# 02-CPU_BOARD.net
KiCad netlist of a schematic drawn in Altium Designer
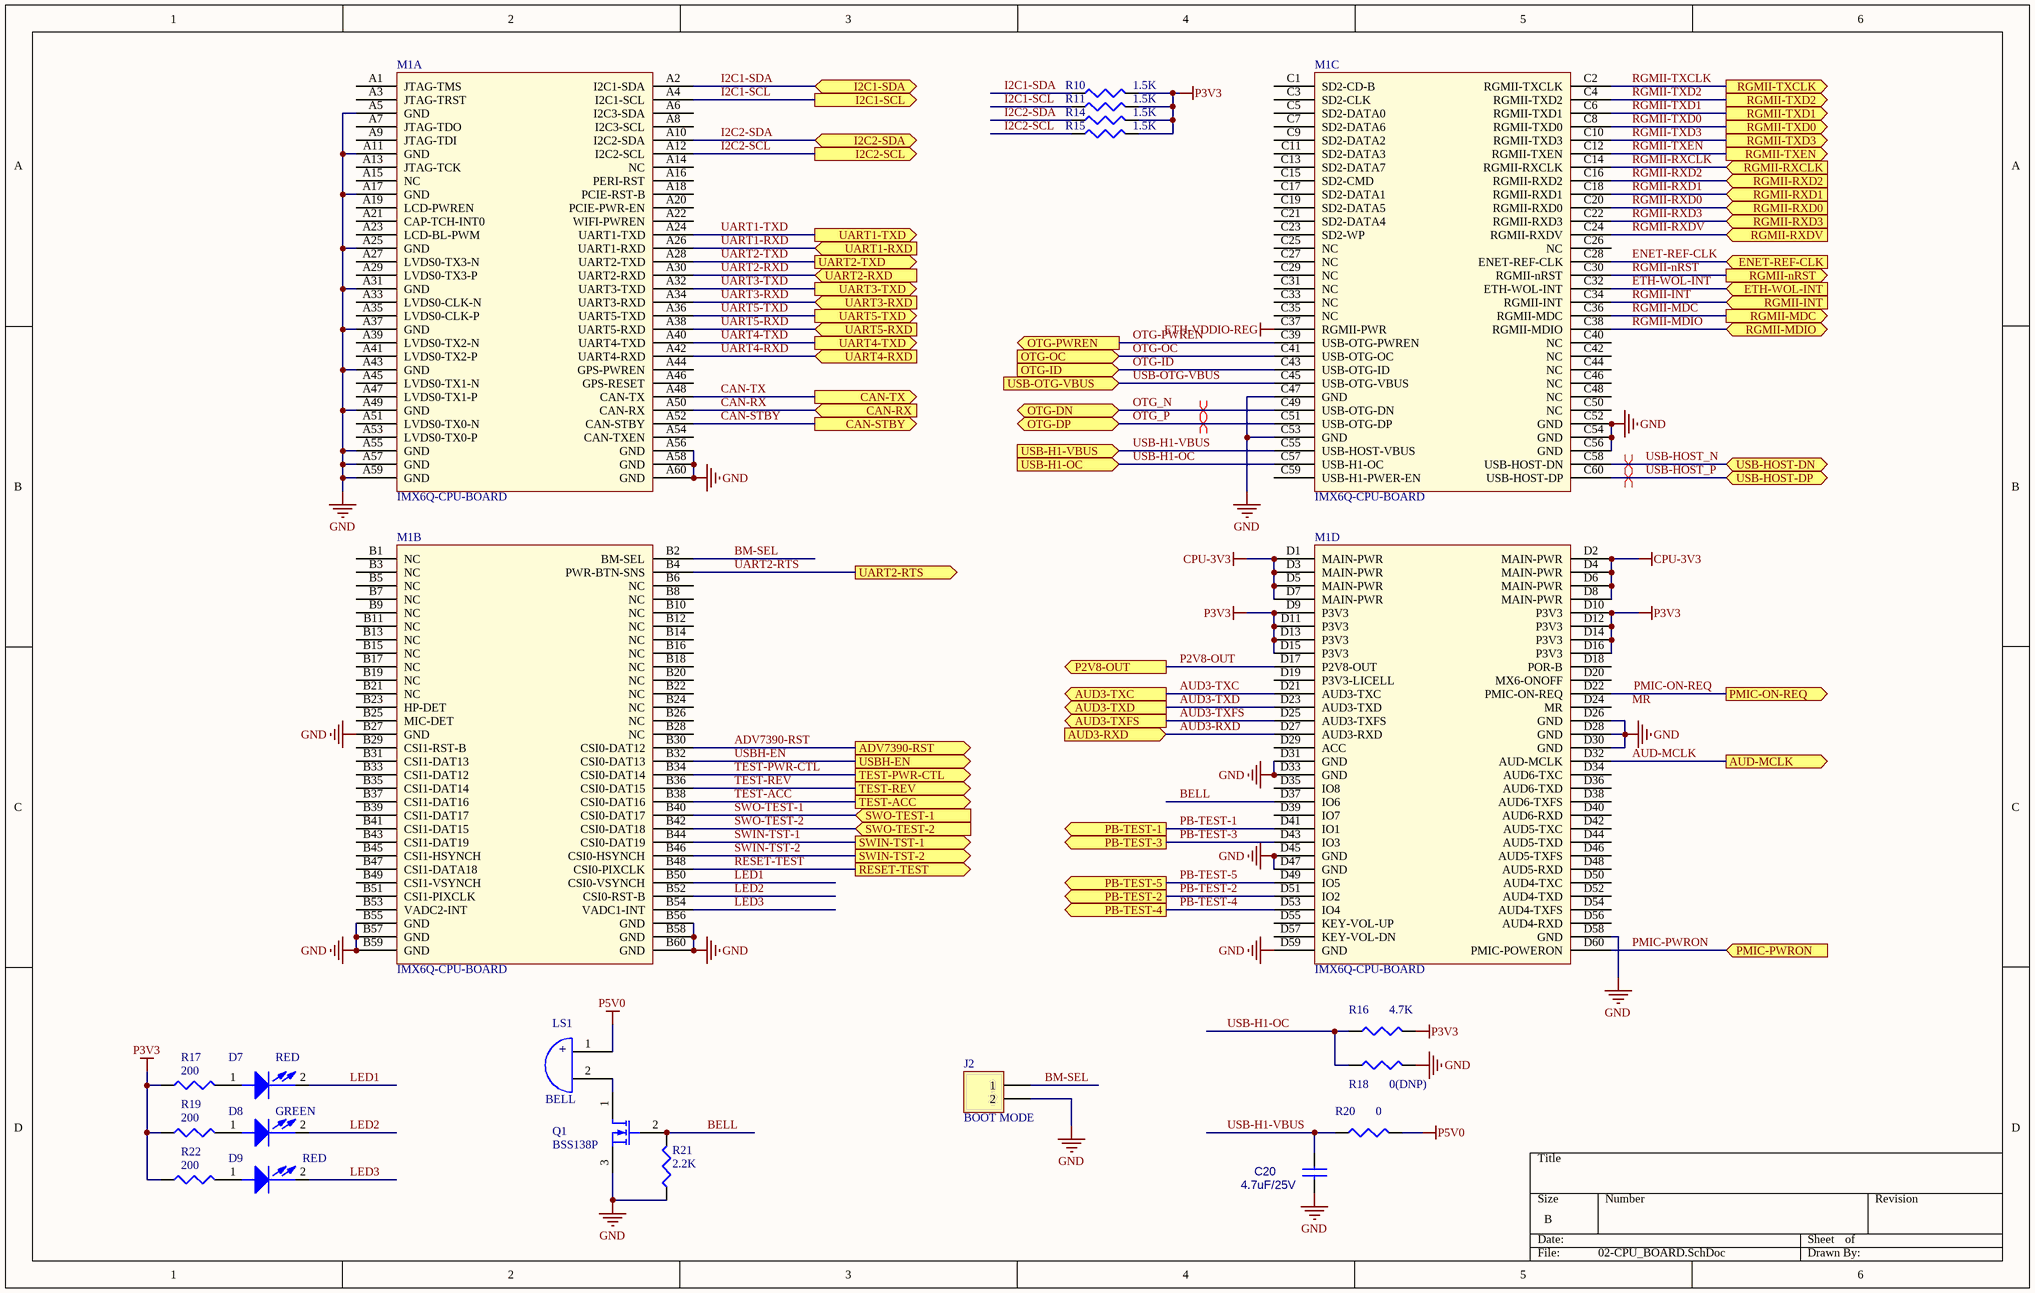
[diagram p0: 02-CPU_BOARD.SchDoc]

(export (version "E")
  (design (tool "Eeschema 10.0.6"))
  (components
    (comp (ref "C20") (value "4.7uF/25V") (libsource (lib "*") (part "CAP_Dup1")))
    (comp (ref "D7") (value "RED") (footprint "LED-3MM") (libsource (lib "*") (part "LN01401_1")))
    (comp (ref "D8") (value "GREEN") (footprint "LED-3MM") (libsource (lib "*") (part "LN01401_1")))
    (comp (ref "D9") (value "RED") (footprint "LED-3MM") (libsource (lib "*") (part "LN01401_1")))
    (comp (ref "J2")
      (value "BOOT MODE")
      (footprint "HDR1X2")
      (description "Header, 2-Pin")
      (fields (field (name "PUBLISHER") "Altium Limited"))
      (libsource (lib "Miscellaneous Connectors") (part "Header 2"))
    )
    (comp (ref "LS1") (value "BELL") (footprint "bell") (libsource (lib "Schlib") (part "BELL")))
    (comp (ref "M1")
      (value "IMX6Q-CPU-BOARD")
      (footprint "IMX6-CPU-BOARD")
      (libsource (lib "Schlib") (part "IMX6Q-CPU-BOARD"))
    )
    (comp (ref "Q1")
      (value "BSS138P")
      (footprint "NPN")
      (description "N-Channel MOSFET")
      (fields (field (name "PUBLISHER") "Altium Limited"))
      (libsource (lib "Miscellaneous Devices") (part "MOSFET-N"))
    )
    (comp (ref "R10") (value "1.5K") (footprint "0402") (libsource (lib "*") (part "CR16-1003FM")))
    (comp (ref "R11") (value "1.5K") (footprint "0402") (libsource (lib "*") (part "CR16-1003FM")))
    (comp (ref "R14") (value "1.5K") (footprint "0402") (libsource (lib "*") (part "CR16-1003FM")))
    (comp (ref "R15") (value "1.5K") (footprint "0402") (libsource (lib "*") (part "CR16-1003FM")))
    (comp (ref "R16") (value "4.7K") (footprint "0402") (libsource (lib "*") (part "CR16-1003FM")))
    (comp (ref "R17")
      (value "200")
      (footprint "0402")
      (description "Resistor")
      (fields (field (name "PUBLISHER") "Altium Limited"))
      (libsource (lib "Miscellaneous Devices") (part "Res3"))
    )
    (comp (ref "R18") (value "0(DNP)") (footprint "0402") (libsource (lib "*") (part "CR16-1003FM")))
    (comp (ref "R19")
      (value "200")
      (footprint "0402")
      (description "Resistor")
      (fields (field (name "PUBLISHER") "Altium Limited"))
      (libsource (lib "Miscellaneous Devices") (part "Res3"))
    )
    (comp (ref "R20") (value "0") (footprint "0402") (libsource (lib "*") (part "CR16-1003FM")))
    (comp (ref "R21")
      (value "2.2K")
      (footprint "0402")
      (description "Resistor")
      (fields (field (name "PUBLISHER") "Altium Limited"))
      (libsource (lib "Miscellaneous Devices") (part "Res3"))
    )
    (comp (ref "R22")
      (value "200")
      (footprint "0402")
      (description "Resistor")
      (fields (field (name "PUBLISHER") "Altium Limited"))
      (libsource (lib "Miscellaneous Devices") (part "Res3"))
    )
  )
  (nets
    (net (code "1") (name "/ADV7390-RST") (class "Default")
      (node (ref "M1") (pin "B30") (pinfunction "CSI0-DAT12_B30") (pintype "passive"))
    )
    (net (code "2") (name "/AUD-MCLK") (class "Default")
      (node (ref "M1") (pin "D32") (pinfunction "AUD-MCLK_D32") (pintype "passive"))
    )
    (net (code "3") (name "/AUD3-RXD") (class "Default")
      (node (ref "M1") (pin "D27") (pinfunction "AUD3-RXD_D27") (pintype "passive"))
    )
    (net (code "4") (name "/AUD3-TXC") (class "Default")
      (node (ref "M1") (pin "D21") (pinfunction "AUD3-TXC_D21") (pintype "passive"))
    )
    (net (code "5") (name "/AUD3-TXD") (class "Default")
      (node (ref "M1") (pin "D23") (pinfunction "AUD3-TXD_D23") (pintype "passive"))
    )
    (net (code "6") (name "/AUD3-TXFS") (class "Default")
      (node (ref "M1") (pin "D25") (pinfunction "AUD3-TXFS_D25") (pintype "passive"))
    )
    (net (code "7") (name "/BELL") (class "Default")
      (node (ref "M1") (pin "D37") (pinfunction "IO6_D37") (pintype "passive"))
      (node (ref "Q1") (pin "2") (pinfunction "G_2") (pintype "passive"))
      (node (ref "R21") (pin "1") (pinfunction "1_1") (pintype "passive"))
    )
    (net (code "8") (name "/BM-SEL") (class "Default")
      (node (ref "J2") (pin "1") (pinfunction "1_1") (pintype "passive"))
      (node (ref "M1") (pin "B2") (pinfunction "BM-SEL_B2") (pintype "passive"))
    )
    (net (code "9") (name "/CAN-RX") (class "Default")
      (node (ref "M1") (pin "A50") (pinfunction "CAN-RX_A50") (pintype "passive"))
    )
    (net (code "10") (name "/CAN-STBY") (class "Default")
      (node (ref "M1") (pin "A52") (pinfunction "CAN-STBY_A52") (pintype "passive"))
    )
    (net (code "11") (name "/CAN-TX") (class "Default")
      (node (ref "M1") (pin "A48") (pinfunction "CAN-TX_A48") (pintype "passive"))
    )
    (net (code "12") (name "/ENET-REF-CLK") (class "Default")
      (node (ref "M1") (pin "C28") (pinfunction "ENET-REF-CLK_C28") (pintype "passive"))
    )
    (net (code "13") (name "/ETH-WOL-INT") (class "Default")
      (node (ref "M1") (pin "C32") (pinfunction "ETH-WOL-INT_C32") (pintype "passive"))
    )
    (net (code "14") (name "/I2C1-SCL") (class "Default")
      (node (ref "M1") (pin "A4") (pinfunction "I2C1-SCL_A4") (pintype "passive"))
      (node (ref "R11") (pin "1") (pinfunction "1_1") (pintype "passive"))
    )
    (net (code "15") (name "/I2C1-SDA") (class "Default")
      (node (ref "M1") (pin "A2") (pinfunction "I2C1-SDA_A2") (pintype "passive"))
      (node (ref "R10") (pin "1") (pinfunction "1_1") (pintype "passive"))
    )
    (net (code "16") (name "/I2C2-SCL") (class "Default")
      (node (ref "M1") (pin "A12") (pinfunction "I2C2-SCL_A12") (pintype "passive"))
      (node (ref "R15") (pin "1") (pinfunction "1_1") (pintype "passive"))
    )
    (net (code "17") (name "/I2C2-SDA") (class "Default")
      (node (ref "M1") (pin "A10") (pinfunction "I2C2-SDA_A10") (pintype "passive"))
      (node (ref "R14") (pin "1") (pinfunction "1_1") (pintype "passive"))
    )
    (net (code "18") (name "/LED1") (class "Default")
      (node (ref "D7") (pin "2") (pinfunction "CATHODE_2") (pintype "passive"))
      (node (ref "M1") (pin "B50") (pinfunction "CSI0-VSYNCH_B50") (pintype "passive"))
    )
    (net (code "19") (name "/LED2") (class "Default")
      (node (ref "D8") (pin "2") (pinfunction "CATHODE_2") (pintype "passive"))
      (node (ref "M1") (pin "B52") (pinfunction "CSI0-RST-B_B52") (pintype "passive"))
    )
    (net (code "20") (name "/LED3") (class "Default")
      (node (ref "D9") (pin "2") (pinfunction "CATHODE_2") (pintype "passive"))
      (node (ref "M1") (pin "B54") (pinfunction "VADC1-INT_B54") (pintype "passive"))
    )
    (net (code "22") (name "/OTG-ID") (class "Default")
      (node (ref "M1") (pin "C43") (pinfunction "USB-OTG-ID_C43") (pintype "passive"))
    )
    (net (code "23") (name "/OTG-OC") (class "Default")
      (node (ref "M1") (pin "C41") (pinfunction "USB-OTG-OC_C41") (pintype "passive"))
    )
    (net (code "24") (name "/OTG-PWREN") (class "Default")
      (node (ref "M1") (pin "C39") (pinfunction "USB-OTG-PWREN_C39") (pintype "passive"))
    )
    (net (code "25") (name "/OTG_N") (class "Default")
      (node (ref "M1") (pin "C49") (pinfunction "USB-OTG-DN_C49") (pintype "passive"))
    )
    (net (code "26") (name "/OTG_P") (class "Default")
      (node (ref "M1") (pin "C51") (pinfunction "USB-OTG-DP_C51") (pintype "passive"))
    )
    (net (code "27") (name "/P2V8-OUT") (class "Default")
      (node (ref "M1") (pin "D17") (pinfunction "P2V8-OUT_D17") (pintype "passive"))
    )
    (net (code "28") (name "/PB-TEST-1") (class "Default")
      (node (ref "M1") (pin "D41") (pinfunction "IO1_D41") (pintype "passive"))
    )
    (net (code "29") (name "/PB-TEST-2") (class "Default")
      (node (ref "M1") (pin "D51") (pinfunction "IO2_D51") (pintype "passive"))
    )
    (net (code "30") (name "/PB-TEST-3") (class "Default")
      (node (ref "M1") (pin "D43") (pinfunction "IO3_D43") (pintype "passive"))
    )
    (net (code "31") (name "/PB-TEST-4") (class "Default")
      (node (ref "M1") (pin "D53") (pinfunction "IO4_D53") (pintype "passive"))
    )
    (net (code "32") (name "/PB-TEST-5") (class "Default")
      (node (ref "M1") (pin "D49") (pinfunction "IO5_D49") (pintype "passive"))
    )
    (net (code "33") (name "/PMIC-ON-REQ") (class "Default")
      (node (ref "M1") (pin "D22") (pinfunction "PMIC-ON-REQ_D22") (pintype "passive"))
    )
    (net (code "34") (name "/PMIC-PWRON") (class "Default")
      (node (ref "M1") (pin "D60") (pinfunction "PMIC-POWERON_D60") (pintype "passive"))
    )
    (net (code "35") (name "/RESET-TEST") (class "Default")
      (node (ref "M1") (pin "B48") (pinfunction "CSI0-PIXCLK_B48") (pintype "passive"))
    )
    (net (code "36") (name "/RGMII-INT") (class "Default")
      (node (ref "M1") (pin "C34") (pinfunction "RGMII-INT_C34") (pintype "passive"))
    )
    (net (code "37") (name "/RGMII-MDC") (class "Default")
      (node (ref "M1") (pin "C36") (pinfunction "RGMII-MDC_C36") (pintype "passive"))
    )
    (net (code "38") (name "/RGMII-MDIO") (class "Default")
      (node (ref "M1") (pin "C38") (pinfunction "RGMII-MDIO_C38") (pintype "passive"))
    )
    (net (code "39") (name "/RGMII-RXCLK") (class "Default")
      (node (ref "M1") (pin "C14") (pinfunction "RGMII-RXCLK_C14") (pintype "passive"))
    )
    (net (code "40") (name "/RGMII-RXD0") (class "Default")
      (node (ref "M1") (pin "C20") (pinfunction "RGMII-RXD0_C20") (pintype "passive"))
    )
    (net (code "41") (name "/RGMII-RXD1") (class "Default")
      (node (ref "M1") (pin "C18") (pinfunction "RGMII-RXD1_C18") (pintype "passive"))
    )
    (net (code "42") (name "/RGMII-RXD2") (class "Default")
      (node (ref "M1") (pin "C16") (pinfunction "RGMII-RXD2_C16") (pintype "passive"))
    )
    (net (code "43") (name "/RGMII-RXD3") (class "Default")
      (node (ref "M1") (pin "C22") (pinfunction "RGMII-RXD3_C22") (pintype "passive"))
    )
    (net (code "44") (name "/RGMII-RXDV") (class "Default")
      (node (ref "M1") (pin "C24") (pinfunction "RGMII-RXDV_C24") (pintype "passive"))
    )
    (net (code "45") (name "/RGMII-TXCLK") (class "Default")
      (node (ref "M1") (pin "C2") (pinfunction "RGMII-TXCLK_C2") (pintype "passive"))
    )
    (net (code "46") (name "/RGMII-TXD0") (class "Default")
      (node (ref "M1") (pin "C8") (pinfunction "RGMII-TXD0_C8") (pintype "passive"))
    )
    (net (code "47") (name "/RGMII-TXD1") (class "Default")
      (node (ref "M1") (pin "C6") (pinfunction "RGMII-TXD1_C6") (pintype "passive"))
    )
    (net (code "48") (name "/RGMII-TXD2") (class "Default")
      (node (ref "M1") (pin "C4") (pinfunction "RGMII-TXD2_C4") (pintype "passive"))
    )
    (net (code "49") (name "/RGMII-TXD3") (class "Default")
      (node (ref "M1") (pin "C10") (pinfunction "RGMII-TXD3_C10") (pintype "passive"))
    )
    (net (code "50") (name "/RGMII-TXEN") (class "Default")
      (node (ref "M1") (pin "C12") (pinfunction "RGMII-TXEN_C12") (pintype "passive"))
    )
    (net (code "51") (name "/RGMII-nRST") (class "Default")
      (node (ref "M1") (pin "C30") (pinfunction "RGMII-nRST_C30") (pintype "passive"))
    )
    (net (code "52") (name "/SWIN-TST-1") (class "Default")
      (node (ref "M1") (pin "B44") (pinfunction "CSI0-DAT19_B44") (pintype "passive"))
    )
    (net (code "53") (name "/SWIN-TST-2") (class "Default")
      (node (ref "M1") (pin "B46") (pinfunction "CSI0-HSYNCH_B46") (pintype "passive"))
    )
    (net (code "54") (name "/SWO-TEST-1") (class "Default")
      (node (ref "M1") (pin "B40") (pinfunction "CSI0-DAT17_B40") (pintype "passive"))
    )
    (net (code "55") (name "/SWO-TEST-2") (class "Default")
      (node (ref "M1") (pin "B42") (pinfunction "CSI0-DAT18_B42") (pintype "passive"))
    )
    (net (code "56") (name "/TEST-ACC") (class "Default")
      (node (ref "M1") (pin "B38") (pinfunction "CSI0-DAT16_B38") (pintype "passive"))
    )
    (net (code "57") (name "/TEST-PWR-CTL") (class "Default")
      (node (ref "M1") (pin "B34") (pinfunction "CSI0-DAT14_B34") (pintype "passive"))
    )
    (net (code "58") (name "/TEST-REV") (class "Default")
      (node (ref "M1") (pin "B36") (pinfunction "CSI0-DAT15_B36") (pintype "passive"))
    )
    (net (code "59") (name "/UART1-RXD") (class "Default")
      (node (ref "M1") (pin "A26") (pinfunction "UART1-RXD_A26") (pintype "passive"))
    )
    (net (code "60") (name "/UART1-TXD") (class "Default")
      (node (ref "M1") (pin "A24") (pinfunction "UART1-TXD_A24") (pintype "passive"))
    )
    (net (code "61") (name "/UART2-RTS") (class "Default")
      (node (ref "M1") (pin "B4") (pinfunction "PWR-BTN-SNS_B4") (pintype "passive"))
    )
    (net (code "62") (name "/UART2-RXD") (class "Default")
      (node (ref "M1") (pin "A30") (pinfunction "UART2-RXD_A30") (pintype "passive"))
    )
    (net (code "63") (name "/UART2-TXD") (class "Default")
      (node (ref "M1") (pin "A28") (pinfunction "UART2-TXD_A28") (pintype "passive"))
    )
    (net (code "64") (name "/UART3-RXD") (class "Default")
      (node (ref "M1") (pin "A34") (pinfunction "UART3-RXD_A34") (pintype "passive"))
    )
    (net (code "65") (name "/UART3-TXD") (class "Default")
      (node (ref "M1") (pin "A32") (pinfunction "UART3-TXD_A32") (pintype "passive"))
    )
    (net (code "66") (name "/UART4-RXD") (class "Default")
      (node (ref "M1") (pin "A42") (pinfunction "UART4-RXD_A42") (pintype "passive"))
    )
    (net (code "67") (name "/UART4-TXD") (class "Default")
      (node (ref "M1") (pin "A40") (pinfunction "UART4-TXD_A40") (pintype "passive"))
    )
    (net (code "68") (name "/UART5-RXD") (class "Default")
      (node (ref "M1") (pin "A38") (pinfunction "UART5-RXD_A38") (pintype "passive"))
    )
    (net (code "69") (name "/UART5-TXD") (class "Default")
      (node (ref "M1") (pin "A36") (pinfunction "UART5-TXD_A36") (pintype "passive"))
    )
    (net (code "70") (name "/USB-H1-OC") (class "Default")
      (node (ref "M1") (pin "C57") (pinfunction "USB-H1-OC_C57") (pintype "passive"))
      (node (ref "R16") (pin "1") (pinfunction "1_1") (pintype "passive"))
      (node (ref "R18") (pin "1") (pinfunction "1_1") (pintype "passive"))
    )
    (net (code "71") (name "/USB-H1-VBUS") (class "Default")
      (node (ref "C20") (pin "1") (pinfunction "1_1") (pintype "passive"))
      (node (ref "M1") (pin "C55") (pinfunction "USB-HOST-VBUS_C55") (pintype "passive"))
      (node (ref "R20") (pin "1") (pinfunction "1_1") (pintype "passive"))
    )
    (net (code "72") (name "/USB-HOST_N") (class "Default")
      (node (ref "M1") (pin "C58") (pinfunction "USB-HOST-DN_C58") (pintype "passive"))
    )
    (net (code "73") (name "/USB-HOST_P") (class "Default")
      (node (ref "M1") (pin "C60") (pinfunction "USB-HOST-DP_C60") (pintype "passive"))
    )
    (net (code "74") (name "/USB-OTG-VBUS") (class "Default")
      (node (ref "M1") (pin "C45") (pinfunction "USB-OTG-VBUS_C45") (pintype "passive"))
    )
    (net (code "75") (name "/USBH-EN") (class "Default")
      (node (ref "M1") (pin "B32") (pinfunction "CSI0-DAT13_B32") (pintype "passive"))
    )
    (net (code "76") (name "CPU-3V3") (class "Default")
      (node (ref "M1") (pin "D1") (pinfunction "MAIN-PWR_D1") (pintype "passive"))
      (node (ref "M1") (pin "D2") (pinfunction "MAIN-PWR_D2") (pintype "passive"))
      (node (ref "M1") (pin "D3") (pinfunction "MAIN-PWR_D3") (pintype "passive"))
      (node (ref "M1") (pin "D4") (pinfunction "MAIN-PWR_D4") (pintype "passive"))
      (node (ref "M1") (pin "D5") (pinfunction "MAIN-PWR_D5") (pintype "passive"))
      (node (ref "M1") (pin "D6") (pinfunction "MAIN-PWR_D6") (pintype "passive"))
      (node (ref "M1") (pin "D7") (pinfunction "MAIN-PWR_D7") (pintype "passive"))
      (node (ref "M1") (pin "D8") (pinfunction "MAIN-PWR_D8") (pintype "passive"))
    )
    (net (code "77") (name "ETH-VDDIO-REG") (class "Default")
      (node (ref "M1") (pin "C37") (pinfunction "RGMII-PWR_C37") (pintype "passive"))
    )
    (net (code "78") (name "GND") (class "Default")
      (node (ref "C20") (pin "2") (pinfunction "2_2") (pintype "passive"))
      (node (ref "J2") (pin "2") (pinfunction "2_2") (pintype "passive"))
      (node (ref "M1") (pin "A11") (pinfunction "GND_A11") (pintype "passive"))
      (node (ref "M1") (pin "A17") (pinfunction "GND_A17") (pintype "passive"))
      (node (ref "M1") (pin "A25") (pinfunction "GND_A25") (pintype "passive"))
      (node (ref "M1") (pin "A31") (pinfunction "GND_A31") (pintype "passive"))
      (node (ref "M1") (pin "A37") (pinfunction "GND_A37") (pintype "passive"))
      (node (ref "M1") (pin "A43") (pinfunction "GND_A43") (pintype "passive"))
      (node (ref "M1") (pin "A49") (pinfunction "GND_A49") (pintype "passive"))
      (node (ref "M1") (pin "A5") (pinfunction "GND_A5") (pintype "passive"))
      (node (ref "M1") (pin "A55") (pinfunction "GND_A55") (pintype "passive"))
      (node (ref "M1") (pin "A56") (pinfunction "GND_A56") (pintype "passive"))
      (node (ref "M1") (pin "A57") (pinfunction "GND_A57") (pintype "passive"))
      (node (ref "M1") (pin "A58") (pinfunction "GND_A58") (pintype "passive"))
      (node (ref "M1") (pin "A59") (pinfunction "GND_A59") (pintype "passive"))
      (node (ref "M1") (pin "A60") (pinfunction "GND_A60") (pintype "passive"))
      (node (ref "M1") (pin "B27") (pinfunction "GND_B27") (pintype "passive"))
      (node (ref "M1") (pin "B55") (pinfunction "GND_B55") (pintype "passive"))
      (node (ref "M1") (pin "B56") (pinfunction "GND_B56") (pintype "passive"))
      (node (ref "M1") (pin "B57") (pinfunction "GND_B57") (pintype "passive"))
      (node (ref "M1") (pin "B58") (pinfunction "GND_B58") (pintype "passive"))
      (node (ref "M1") (pin "B59") (pinfunction "GND_B59") (pintype "passive"))
      (node (ref "M1") (pin "B60") (pinfunction "GND_B60") (pintype "passive"))
      (node (ref "M1") (pin "C47") (pinfunction "GND_C47") (pintype "passive"))
      (node (ref "M1") (pin "C52") (pinfunction "GND_C52") (pintype "passive"))
      (node (ref "M1") (pin "C53") (pinfunction "GND_C53") (pintype "passive"))
      (node (ref "M1") (pin "C54") (pinfunction "GND_C54") (pintype "passive"))
      (node (ref "M1") (pin "C56") (pinfunction "GND_C56") (pintype "passive"))
      (node (ref "M1") (pin "D26") (pinfunction "GND_D26") (pintype "passive"))
      (node (ref "M1") (pin "D28") (pinfunction "GND_D28") (pintype "passive"))
      (node (ref "M1") (pin "D30") (pinfunction "GND_D30") (pintype "passive"))
      (node (ref "M1") (pin "D31") (pinfunction "GND_D31") (pintype "passive"))
      (node (ref "M1") (pin "D33") (pinfunction "GND_D33") (pintype "passive"))
      (node (ref "M1") (pin "D45") (pinfunction "GND_D45") (pintype "passive"))
      (node (ref "M1") (pin "D47") (pinfunction "GND_D47") (pintype "passive"))
      (node (ref "M1") (pin "D58") (pinfunction "GND_D58") (pintype "passive"))
      (node (ref "M1") (pin "D59") (pinfunction "GND_D59") (pintype "passive"))
      (node (ref "Q1") (pin "3") (pinfunction "S_3") (pintype "passive"))
      (node (ref "R18") (pin "2") (pinfunction "2_2") (pintype "passive"))
      (node (ref "R21") (pin "2") (pinfunction "2_2") (pintype "passive"))
    )
    (net (code "79") (name "Net-(D7-ANODE)") (class "Default")
      (node (ref "D7") (pin "1") (pinfunction "ANODE_1") (pintype "passive"))
      (node (ref "R17") (pin "2") (pinfunction "2_2") (pintype "passive"))
    )
    (net (code "80") (name "Net-(D8-ANODE)") (class "Default")
      (node (ref "D8") (pin "1") (pinfunction "ANODE_1") (pintype "passive"))
      (node (ref "R19") (pin "2") (pinfunction "2_2") (pintype "passive"))
    )
    (net (code "81") (name "Net-(D9-ANODE)") (class "Default")
      (node (ref "D9") (pin "1") (pinfunction "ANODE_1") (pintype "passive"))
      (node (ref "R22") (pin "2") (pinfunction "2_2") (pintype "passive"))
    )
    (net (code "82") (name "Net-(Q1-D)") (class "Default")
      (node (ref "LS1") (pin "2") (pinfunction "2_2") (pintype "passive"))
      (node (ref "Q1") (pin "1") (pinfunction "D_1") (pintype "passive"))
    )
    (net (code "83") (name "P3V3") (class "Default")
      (node (ref "M1") (pin "D10") (pinfunction "P3V3_D10") (pintype "passive"))
      (node (ref "M1") (pin "D11") (pinfunction "P3V3_D11") (pintype "passive"))
      (node (ref "M1") (pin "D12") (pinfunction "P3V3_D12") (pintype "passive"))
      (node (ref "M1") (pin "D13") (pinfunction "P3V3_D13") (pintype "passive"))
      (node (ref "M1") (pin "D14") (pinfunction "P3V3_D14") (pintype "passive"))
      (node (ref "M1") (pin "D15") (pinfunction "P3V3_D15") (pintype "passive"))
      (node (ref "M1") (pin "D16") (pinfunction "P3V3_D16") (pintype "passive"))
      (node (ref "M1") (pin "D9") (pinfunction "P3V3_D9") (pintype "passive"))
      (node (ref "R10") (pin "2") (pinfunction "2_2") (pintype "passive"))
      (node (ref "R11") (pin "2") (pinfunction "2_2") (pintype "passive"))
      (node (ref "R14") (pin "2") (pinfunction "2_2") (pintype "passive"))
      (node (ref "R15") (pin "2") (pinfunction "2_2") (pintype "passive"))
      (node (ref "R16") (pin "2") (pinfunction "2_2") (pintype "passive"))
      (node (ref "R17") (pin "1") (pinfunction "1_1") (pintype "passive"))
      (node (ref "R19") (pin "1") (pinfunction "1_1") (pintype "passive"))
      (node (ref "R22") (pin "1") (pinfunction "1_1") (pintype "passive"))
    )
    (net (code "84") (name "P5V0") (class "Default")
      (node (ref "LS1") (pin "1") (pinfunction "1_1") (pintype "passive"))
      (node (ref "R20") (pin "2") (pinfunction "2_2") (pintype "passive"))
    )
    (net (code "85") (name "unconnected-(M1A-CAN-TXEN-PadA54)") (class "Default")
      (node (ref "M1") (pin "A54") (pinfunction "CAN-TXEN_A54") (pintype "passive"))
    )
    (net (code "86") (name "unconnected-(M1A-CAP-TCH-INT0-PadA21)") (class "Default")
      (node (ref "M1") (pin "A21") (pinfunction "CAP-TCH-INT0_A21") (pintype "passive"))
    )
    (net (code "87") (name "unconnected-(M1A-GPS-PWREN-PadA44)") (class "Default")
      (node (ref "M1") (pin "A44") (pinfunction "GPS-PWREN_A44") (pintype "passive"))
    )
    (net (code "88") (name "unconnected-(M1A-GPS-RESET-PadA46)") (class "Default")
      (node (ref "M1") (pin "A46") (pinfunction "GPS-RESET_A46") (pintype "passive"))
    )
    (net (code "89") (name "unconnected-(M1A-I2C3-SCL-PadA8)") (class "Default")
      (node (ref "M1") (pin "A8") (pinfunction "I2C3-SCL_A8") (pintype "passive"))
    )
    (net (code "90") (name "unconnected-(M1A-I2C3-SDA-PadA6)") (class "Default")
      (node (ref "M1") (pin "A6") (pinfunction "I2C3-SDA_A6") (pintype "passive"))
    )
    (net (code "91") (name "unconnected-(M1A-JTAG-TCK-PadA13)") (class "Default")
      (node (ref "M1") (pin "A13") (pinfunction "JTAG-TCK_A13") (pintype "passive"))
    )
    (net (code "92") (name "unconnected-(M1A-JTAG-TDI-PadA9)") (class "Default")
      (node (ref "M1") (pin "A9") (pinfunction "JTAG-TDI_A9") (pintype "passive"))
    )
    (net (code "93") (name "unconnected-(M1A-JTAG-TDO-PadA7)") (class "Default")
      (node (ref "M1") (pin "A7") (pinfunction "JTAG-TDO_A7") (pintype "passive"))
    )
    (net (code "94") (name "unconnected-(M1A-JTAG-TMS-PadA1)") (class "Default")
      (node (ref "M1") (pin "A1") (pinfunction "JTAG-TMS_A1") (pintype "passive"))
    )
    (net (code "95") (name "unconnected-(M1A-JTAG-TRST-PadA3)") (class "Default")
      (node (ref "M1") (pin "A3") (pinfunction "JTAG-TRST_A3") (pintype "passive"))
    )
    (net (code "96") (name "unconnected-(M1A-LCD-BL-PWM-PadA23)") (class "Default")
      (node (ref "M1") (pin "A23") (pinfunction "LCD-BL-PWM_A23") (pintype "passive"))
    )
    (net (code "97") (name "unconnected-(M1A-LCD-PWREN-PadA19)") (class "Default")
      (node (ref "M1") (pin "A19") (pinfunction "LCD-PWREN_A19") (pintype "passive"))
    )
    (net (code "98") (name "unconnected-(M1A-LVDS0-CLK-N-PadA33)") (class "Default")
      (node (ref "M1") (pin "A33") (pinfunction "LVDS0-CLK-N_A33") (pintype "passive"))
    )
    (net (code "99") (name "unconnected-(M1A-LVDS0-CLK-P-PadA35)") (class "Default")
      (node (ref "M1") (pin "A35") (pinfunction "LVDS0-CLK-P_A35") (pintype "passive"))
    )
    (net (code "100") (name "unconnected-(M1A-LVDS0-TX0-N-PadA51)") (class "Default")
      (node (ref "M1") (pin "A51") (pinfunction "LVDS0-TX0-N_A51") (pintype "passive"))
    )
    (net (code "101") (name "unconnected-(M1A-LVDS0-TX0-P-PadA53)") (class "Default")
      (node (ref "M1") (pin "A53") (pinfunction "LVDS0-TX0-P_A53") (pintype "passive"))
    )
    (net (code "102") (name "unconnected-(M1A-LVDS0-TX1-N-PadA45)") (class "Default")
      (node (ref "M1") (pin "A45") (pinfunction "LVDS0-TX1-N_A45") (pintype "passive"))
    )
    (net (code "103") (name "unconnected-(M1A-LVDS0-TX1-P-PadA47)") (class "Default")
      (node (ref "M1") (pin "A47") (pinfunction "LVDS0-TX1-P_A47") (pintype "passive"))
    )
    (net (code "104") (name "unconnected-(M1A-LVDS0-TX2-N-PadA39)") (class "Default")
      (node (ref "M1") (pin "A39") (pinfunction "LVDS0-TX2-N_A39") (pintype "passive"))
    )
    (net (code "105") (name "unconnected-(M1A-LVDS0-TX2-P-PadA41)") (class "Default")
      (node (ref "M1") (pin "A41") (pinfunction "LVDS0-TX2-P_A41") (pintype "passive"))
    )
    (net (code "106") (name "unconnected-(M1A-LVDS0-TX3-N-PadA27)") (class "Default")
      (node (ref "M1") (pin "A27") (pinfunction "LVDS0-TX3-N_A27") (pintype "passive"))
    )
    (net (code "107") (name "unconnected-(M1A-LVDS0-TX3-P-PadA29)") (class "Default")
      (node (ref "M1") (pin "A29") (pinfunction "LVDS0-TX3-P_A29") (pintype "passive"))
    )
    (net (code "108") (name "unconnected-(M1A-NC-PadA14)") (class "Default")
      (node (ref "M1") (pin "A14") (pinfunction "NC_A14") (pintype "passive"))
    )
    (net (code "109") (name "unconnected-(M1A-NC-PadA15)") (class "Default")
      (node (ref "M1") (pin "A15") (pinfunction "NC_A15") (pintype "passive"))
    )
    (net (code "110") (name "unconnected-(M1A-PCIE-PWR-EN-PadA20)") (class "Default")
      (node (ref "M1") (pin "A20") (pinfunction "PCIE-PWR-EN_A20") (pintype "passive"))
    )
    (net (code "111") (name "unconnected-(M1A-PCIE-RST-B-PadA18)") (class "Default")
      (node (ref "M1") (pin "A18") (pinfunction "PCIE-RST-B_A18") (pintype "passive"))
    )
    (net (code "112") (name "unconnected-(M1A-PERI-RST-PadA16)") (class "Default")
      (node (ref "M1") (pin "A16") (pinfunction "PERI-RST_A16") (pintype "passive"))
    )
    (net (code "113") (name "unconnected-(M1A-WIFI-PWREN-PadA22)") (class "Default")
      (node (ref "M1") (pin "A22") (pinfunction "WIFI-PWREN_A22") (pintype "passive"))
    )
    (net (code "114") (name "unconnected-(M1B-CSI1-DAT12-PadB33)") (class "Default")
      (node (ref "M1") (pin "B33") (pinfunction "CSI1-DAT12_B33") (pintype "passive"))
    )
    (net (code "115") (name "unconnected-(M1B-CSI1-DAT13-PadB31)") (class "Default")
      (node (ref "M1") (pin "B31") (pinfunction "CSI1-DAT13_B31") (pintype "passive"))
    )
    (net (code "116") (name "unconnected-(M1B-CSI1-DAT14-PadB35)") (class "Default")
      (node (ref "M1") (pin "B35") (pinfunction "CSI1-DAT14_B35") (pintype "passive"))
    )
    (net (code "117") (name "unconnected-(M1B-CSI1-DAT15-PadB41)") (class "Default")
      (node (ref "M1") (pin "B41") (pinfunction "CSI1-DAT15_B41") (pintype "passive"))
    )
    (net (code "118") (name "unconnected-(M1B-CSI1-DAT16-PadB37)") (class "Default")
      (node (ref "M1") (pin "B37") (pinfunction "CSI1-DAT16_B37") (pintype "passive"))
    )
    (net (code "119") (name "unconnected-(M1B-CSI1-DAT17-PadB39)") (class "Default")
      (node (ref "M1") (pin "B39") (pinfunction "CSI1-DAT17_B39") (pintype "passive"))
    )
    (net (code "120") (name "unconnected-(M1B-CSI1-DAT19-PadB43)") (class "Default")
      (node (ref "M1") (pin "B43") (pinfunction "CSI1-DAT19_B43") (pintype "passive"))
    )
    (net (code "121") (name "unconnected-(M1B-CSI1-DATA18-PadB47)") (class "Default")
      (node (ref "M1") (pin "B47") (pinfunction "CSI1-DATA18_B47") (pintype "passive"))
    )
    (net (code "122") (name "unconnected-(M1B-CSI1-HSYNCH-PadB45)") (class "Default")
      (node (ref "M1") (pin "B45") (pinfunction "CSI1-HSYNCH_B45") (pintype "passive"))
    )
    (net (code "123") (name "unconnected-(M1B-CSI1-PIXCLK-PadB51)") (class "Default")
      (node (ref "M1") (pin "B51") (pinfunction "CSI1-PIXCLK_B51") (pintype "passive"))
    )
    (net (code "124") (name "unconnected-(M1B-CSI1-RST-B-PadB29)") (class "Default")
      (node (ref "M1") (pin "B29") (pinfunction "CSI1-RST-B_B29") (pintype "passive"))
    )
    (net (code "125") (name "unconnected-(M1B-CSI1-VSYNCH-PadB49)") (class "Default")
      (node (ref "M1") (pin "B49") (pinfunction "CSI1-VSYNCH_B49") (pintype "passive"))
    )
    (net (code "126") (name "unconnected-(M1B-HP-DET-PadB23)") (class "Default")
      (node (ref "M1") (pin "B23") (pinfunction "HP-DET_B23") (pintype "passive"))
    )
    (net (code "127") (name "unconnected-(M1B-MIC-DET-PadB25)") (class "Default")
      (node (ref "M1") (pin "B25") (pinfunction "MIC-DET_B25") (pintype "passive"))
    )
    (net (code "128") (name "unconnected-(M1B-NC-PadB1)") (class "Default")
      (node (ref "M1") (pin "B1") (pinfunction "NC_B1") (pintype "passive"))
    )
    (net (code "129") (name "unconnected-(M1B-NC-PadB3)") (class "Default")
      (node (ref "M1") (pin "B3") (pinfunction "NC_B3") (pintype "passive"))
    )
    (net (code "130") (name "unconnected-(M1B-NC-PadB5)") (class "Default")
      (node (ref "M1") (pin "B5") (pinfunction "NC_B5") (pintype "passive"))
    )
    (net (code "131") (name "unconnected-(M1B-NC-PadB6)") (class "Default")
      (node (ref "M1") (pin "B6") (pinfunction "NC_B6") (pintype "passive"))
    )
    (net (code "132") (name "unconnected-(M1B-NC-PadB7)") (class "Default")
      (node (ref "M1") (pin "B7") (pinfunction "NC_B7") (pintype "passive"))
    )
    (net (code "133") (name "unconnected-(M1B-NC-PadB8)") (class "Default")
      (node (ref "M1") (pin "B8") (pinfunction "NC_B8") (pintype "passive"))
    )
    (net (code "134") (name "unconnected-(M1B-NC-PadB9)") (class "Default")
      (node (ref "M1") (pin "B9") (pinfunction "NC_B9") (pintype "passive"))
    )
    (net (code "135") (name "unconnected-(M1B-NC-PadB10)") (class "Default")
      (node (ref "M1") (pin "B10") (pinfunction "NC_B10") (pintype "passive"))
    )
    (net (code "136") (name "unconnected-(M1B-NC-PadB11)") (class "Default")
      (node (ref "M1") (pin "B11") (pinfunction "NC_B11") (pintype "passive"))
    )
    (net (code "137") (name "unconnected-(M1B-NC-PadB12)") (class "Default")
      (node (ref "M1") (pin "B12") (pinfunction "NC_B12") (pintype "passive"))
    )
    (net (code "138") (name "unconnected-(M1B-NC-PadB13)") (class "Default")
      (node (ref "M1") (pin "B13") (pinfunction "NC_B13") (pintype "passive"))
    )
    (net (code "139") (name "unconnected-(M1B-NC-PadB14)") (class "Default")
      (node (ref "M1") (pin "B14") (pinfunction "NC_B14") (pintype "passive"))
    )
    (net (code "140") (name "unconnected-(M1B-NC-PadB15)") (class "Default")
      (node (ref "M1") (pin "B15") (pinfunction "NC_B15") (pintype "passive"))
    )
    (net (code "141") (name "unconnected-(M1B-NC-PadB16)") (class "Default")
      (node (ref "M1") (pin "B16") (pinfunction "NC_B16") (pintype "passive"))
    )
    (net (code "142") (name "unconnected-(M1B-NC-PadB17)") (class "Default")
      (node (ref "M1") (pin "B17") (pinfunction "NC_B17") (pintype "passive"))
    )
    (net (code "143") (name "unconnected-(M1B-NC-PadB18)") (class "Default")
      (node (ref "M1") (pin "B18") (pinfunction "NC_B18") (pintype "passive"))
    )
    (net (code "144") (name "unconnected-(M1B-NC-PadB19)") (class "Default")
      (node (ref "M1") (pin "B19") (pinfunction "NC_B19") (pintype "passive"))
    )
    (net (code "145") (name "unconnected-(M1B-NC-PadB20)") (class "Default")
      (node (ref "M1") (pin "B20") (pinfunction "NC_B20") (pintype "passive"))
    )
    (net (code "146") (name "unconnected-(M1B-NC-PadB21)") (class "Default")
      (node (ref "M1") (pin "B21") (pinfunction "NC_B21") (pintype "passive"))
    )
    (net (code "147") (name "unconnected-(M1B-NC-PadB22)") (class "Default")
      (node (ref "M1") (pin "B22") (pinfunction "NC_B22") (pintype "passive"))
    )
    (net (code "148") (name "unconnected-(M1B-NC-PadB24)") (class "Default")
      (node (ref "M1") (pin "B24") (pinfunction "NC_B24") (pintype "passive"))
    )
    (net (code "149") (name "unconnected-(M1B-NC-PadB26)") (class "Default")
      (node (ref "M1") (pin "B26") (pinfunction "NC_B26") (pintype "passive"))
    )
    (net (code "150") (name "unconnected-(M1B-NC-PadB28)") (class "Default")
      (node (ref "M1") (pin "B28") (pinfunction "NC_B28") (pintype "passive"))
    )
    (net (code "151") (name "unconnected-(M1B-VADC2-INT-PadB53)") (class "Default")
      (node (ref "M1") (pin "B53") (pinfunction "VADC2-INT_B53") (pintype "passive"))
    )
    (net (code "152") (name "unconnected-(M1C-NC-PadC25)") (class "Default")
      (node (ref "M1") (pin "C25") (pinfunction "NC_C25") (pintype "passive"))
    )
    (net (code "153") (name "unconnected-(M1C-NC-PadC26)") (class "Default")
      (node (ref "M1") (pin "C26") (pinfunction "NC_C26") (pintype "passive"))
    )
    (net (code "154") (name "unconnected-(M1C-NC-PadC27)") (class "Default")
      (node (ref "M1") (pin "C27") (pinfunction "NC_C27") (pintype "passive"))
    )
    (net (code "155") (name "unconnected-(M1C-NC-PadC29)") (class "Default")
      (node (ref "M1") (pin "C29") (pinfunction "NC_C29") (pintype "passive"))
    )
    (net (code "156") (name "unconnected-(M1C-NC-PadC31)") (class "Default")
      (node (ref "M1") (pin "C31") (pinfunction "NC_C31") (pintype "passive"))
    )
    (net (code "157") (name "unconnected-(M1C-NC-PadC33)") (class "Default")
      (node (ref "M1") (pin "C33") (pinfunction "NC_C33") (pintype "passive"))
    )
    (net (code "158") (name "unconnected-(M1C-NC-PadC35)") (class "Default")
      (node (ref "M1") (pin "C35") (pinfunction "NC_C35") (pintype "passive"))
    )
    (net (code "159") (name "unconnected-(M1C-NC-PadC40)") (class "Default")
      (node (ref "M1") (pin "C40") (pinfunction "NC_C40") (pintype "passive"))
    )
    (net (code "160") (name "unconnected-(M1C-NC-PadC42)") (class "Default")
      (node (ref "M1") (pin "C42") (pinfunction "NC_C42") (pintype "passive"))
    )
    (net (code "161") (name "unconnected-(M1C-NC-PadC44)") (class "Default")
      (node (ref "M1") (pin "C44") (pinfunction "NC_C44") (pintype "passive"))
    )
    (net (code "162") (name "unconnected-(M1C-NC-PadC46)") (class "Default")
      (node (ref "M1") (pin "C46") (pinfunction "NC_C46") (pintype "passive"))
    )
    (net (code "163") (name "unconnected-(M1C-NC-PadC48)") (class "Default")
      (node (ref "M1") (pin "C48") (pinfunction "NC_C48") (pintype "passive"))
    )
    (net (code "164") (name "unconnected-(M1C-NC-PadC50)") (class "Default")
      (node (ref "M1") (pin "C50") (pinfunction "NC_C50") (pintype "passive"))
    )
    (net (code "165") (name "unconnected-(M1C-SD2-CD-B-PadC1)") (class "Default")
      (node (ref "M1") (pin "C1") (pinfunction "SD2-CD-B_C1") (pintype "passive"))
    )
    (net (code "166") (name "unconnected-(M1C-SD2-CLK-PadC3)") (class "Default")
      (node (ref "M1") (pin "C3") (pinfunction "SD2-CLK_C3") (pintype "passive"))
    )
    (net (code "167") (name "unconnected-(M1C-SD2-CMD-PadC15)") (class "Default")
      (node (ref "M1") (pin "C15") (pinfunction "SD2-CMD_C15") (pintype "passive"))
    )
    (net (code "168") (name "unconnected-(M1C-SD2-DATA0-PadC5)") (class "Default")
      (node (ref "M1") (pin "C5") (pinfunction "SD2-DATA0_C5") (pintype "passive"))
    )
    (net (code "169") (name "unconnected-(M1C-SD2-DATA1-PadC17)") (class "Default")
      (node (ref "M1") (pin "C17") (pinfunction "SD2-DATA1_C17") (pintype "passive"))
    )
    (net (code "170") (name "unconnected-(M1C-SD2-DATA2-PadC9)") (class "Default")
      (node (ref "M1") (pin "C9") (pinfunction "SD2-DATA2_C9") (pintype "passive"))
    )
    (net (code "171") (name "unconnected-(M1C-SD2-DATA3-PadC11)") (class "Default")
      (node (ref "M1") (pin "C11") (pinfunction "SD2-DATA3_C11") (pintype "passive"))
    )
    (net (code "172") (name "unconnected-(M1C-SD2-DATA4-PadC21)") (class "Default")
      (node (ref "M1") (pin "C21") (pinfunction "SD2-DATA4_C21") (pintype "passive"))
    )
    (net (code "173") (name "unconnected-(M1C-SD2-DATA5-PadC19)") (class "Default")
      (node (ref "M1") (pin "C19") (pinfunction "SD2-DATA5_C19") (pintype "passive"))
    )
    (net (code "174") (name "unconnected-(M1C-SD2-DATA6-PadC7)") (class "Default")
      (node (ref "M1") (pin "C7") (pinfunction "SD2-DATA6_C7") (pintype "passive"))
    )
    (net (code "175") (name "unconnected-(M1C-SD2-DATA7-PadC13)") (class "Default")
      (node (ref "M1") (pin "C13") (pinfunction "SD2-DATA7_C13") (pintype "passive"))
    )
    (net (code "176") (name "unconnected-(M1C-SD2-WP-PadC23)") (class "Default")
      (node (ref "M1") (pin "C23") (pinfunction "SD2-WP_C23") (pintype "passive"))
    )
    (net (code "177") (name "unconnected-(M1C-USB-H1-PWER-EN-PadC59)") (class "Default")
      (node (ref "M1") (pin "C59") (pinfunction "USB-H1-PWER-EN_C59") (pintype "passive"))
    )
    (net (code "178") (name "unconnected-(M1D-ACC-PadD29)") (class "Default")
      (node (ref "M1") (pin "D29") (pinfunction "ACC_D29") (pintype "passive"))
    )
    (net (code "179") (name "unconnected-(M1D-AUD4-RXD-PadD56)") (class "Default")
      (node (ref "M1") (pin "D56") (pinfunction "AUD4-RXD_D56") (pintype "passive"))
    )
    (net (code "180") (name "unconnected-(M1D-AUD4-TXC-PadD50)") (class "Default")
      (node (ref "M1") (pin "D50") (pinfunction "AUD4-TXC_D50") (pintype "passive"))
    )
    (net (code "181") (name "unconnected-(M1D-AUD4-TXD-PadD52)") (class "Default")
      (node (ref "M1") (pin "D52") (pinfunction "AUD4-TXD_D52") (pintype "passive"))
    )
    (net (code "182") (name "unconnected-(M1D-AUD4-TXFS-PadD54)") (class "Default")
      (node (ref "M1") (pin "D54") (pinfunction "AUD4-TXFS_D54") (pintype "passive"))
    )
    (net (code "183") (name "unconnected-(M1D-AUD5-RXD-PadD48)") (class "Default")
      (node (ref "M1") (pin "D48") (pinfunction "AUD5-RXD_D48") (pintype "passive"))
    )
    (net (code "184") (name "unconnected-(M1D-AUD5-TXC-PadD42)") (class "Default")
      (node (ref "M1") (pin "D42") (pinfunction "AUD5-TXC_D42") (pintype "passive"))
    )
    (net (code "185") (name "unconnected-(M1D-AUD5-TXD-PadD44)") (class "Default")
      (node (ref "M1") (pin "D44") (pinfunction "AUD5-TXD_D44") (pintype "passive"))
    )
    (net (code "186") (name "unconnected-(M1D-AUD5-TXFS-PadD46)") (class "Default")
      (node (ref "M1") (pin "D46") (pinfunction "AUD5-TXFS_D46") (pintype "passive"))
    )
    (net (code "187") (name "unconnected-(M1D-AUD6-RXD-PadD40)") (class "Default")
      (node (ref "M1") (pin "D40") (pinfunction "AUD6-RXD_D40") (pintype "passive"))
    )
    (net (code "188") (name "unconnected-(M1D-AUD6-TXC-PadD34)") (class "Default")
      (node (ref "M1") (pin "D34") (pinfunction "AUD6-TXC_D34") (pintype "passive"))
    )
    (net (code "189") (name "unconnected-(M1D-AUD6-TXD-PadD36)") (class "Default")
      (node (ref "M1") (pin "D36") (pinfunction "AUD6-TXD_D36") (pintype "passive"))
    )
    (net (code "190") (name "unconnected-(M1D-AUD6-TXFS-PadD38)") (class "Default")
      (node (ref "M1") (pin "D38") (pinfunction "AUD6-TXFS_D38") (pintype "passive"))
    )
    (net (code "191") (name "unconnected-(M1D-IO7-PadD39)") (class "Default")
      (node (ref "M1") (pin "D39") (pinfunction "IO7_D39") (pintype "passive"))
    )
    (net (code "192") (name "unconnected-(M1D-IO8-PadD35)") (class "Default")
      (node (ref "M1") (pin "D35") (pinfunction "IO8_D35") (pintype "passive"))
    )
    (net (code "193") (name "unconnected-(M1D-KEY-VOL-DN-PadD57)") (class "Default")
      (node (ref "M1") (pin "D57") (pinfunction "KEY-VOL-DN_D57") (pintype "passive"))
    )
    (net (code "194") (name "unconnected-(M1D-KEY-VOL-UP-PadD55)") (class "Default")
      (node (ref "M1") (pin "D55") (pinfunction "KEY-VOL-UP_D55") (pintype "passive"))
    )
    (net (code "195") (name "unconnected-(M1D-MR-PadD24)") (class "Default")
      (node (ref "M1") (pin "D24") (pinfunction "MR_D24") (pintype "passive"))
    )
    (net (code "196") (name "unconnected-(M1D-MX6-ONOFF-PadD20)") (class "Default")
      (node (ref "M1") (pin "D20") (pinfunction "MX6-ONOFF_D20") (pintype "passive"))
    )
    (net (code "197") (name "unconnected-(M1D-P3V3-LICELL-PadD19)") (class "Default")
      (node (ref "M1") (pin "D19") (pinfunction "P3V3-LICELL_D19") (pintype "passive"))
    )
    (net (code "198") (name "unconnected-(M1D-POR-B-PadD18)") (class "Default")
      (node (ref "M1") (pin "D18") (pinfunction "POR-B_D18") (pintype "passive"))
    )
  )
)
